# m13temp.net
KiCad netlist of a schematic drawn in Altium Designer
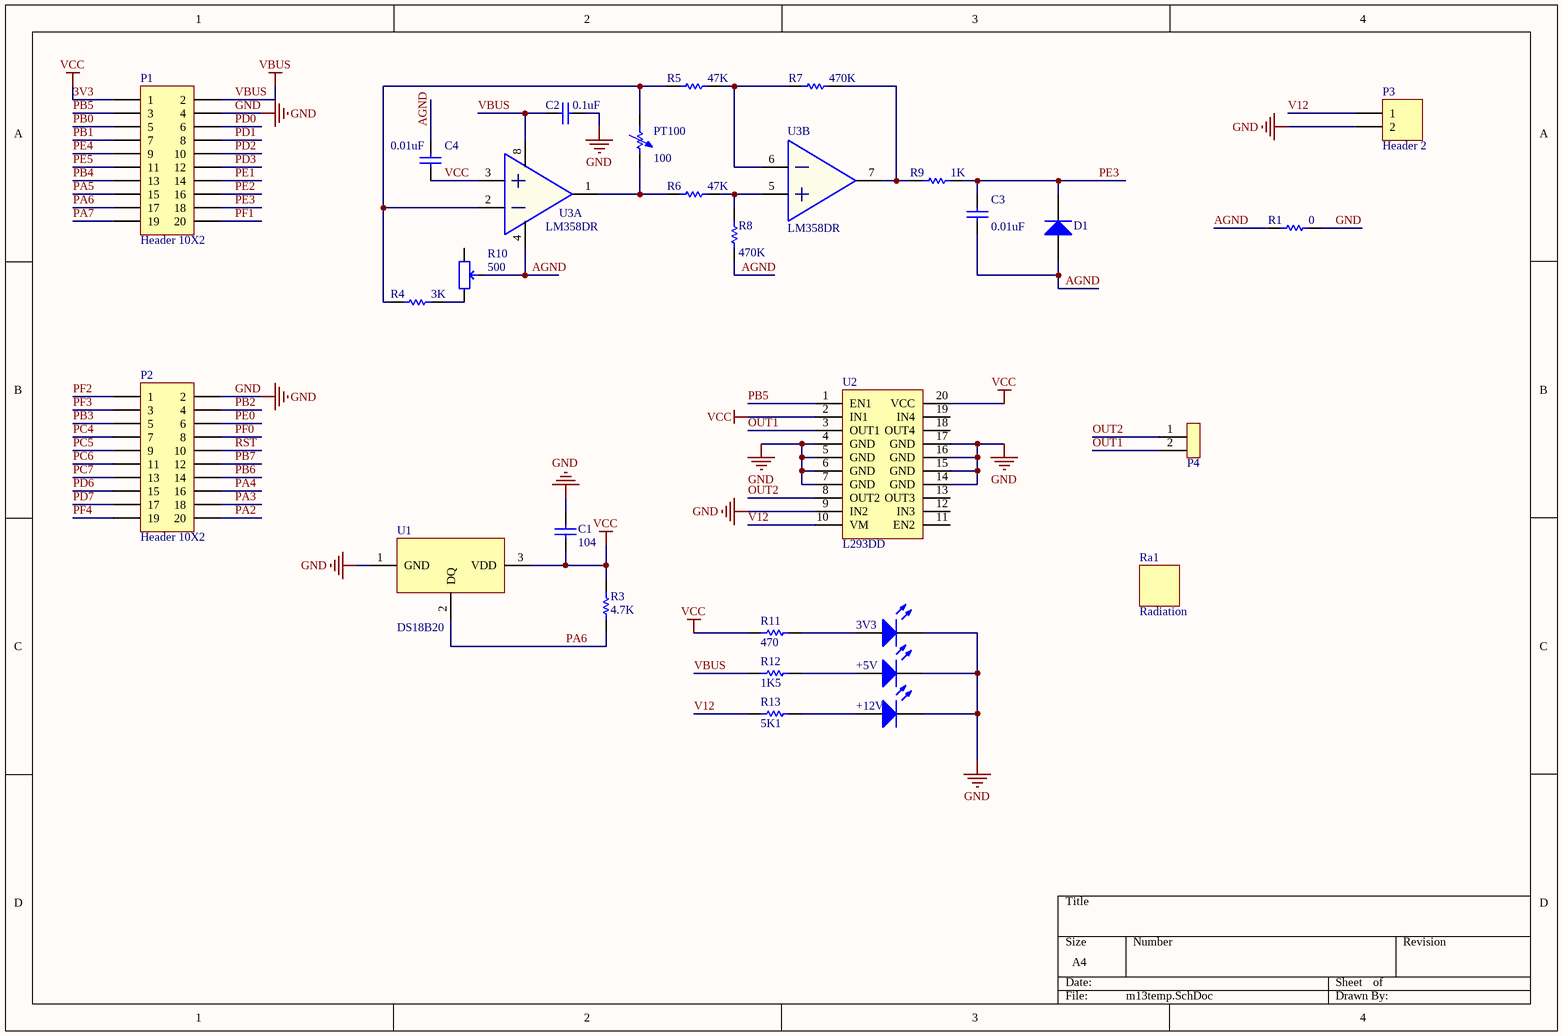
[diagram p0: m13temp.SchDoc]

(export (version "E")
  (design (tool "Eeschema 10.0.6"))
  (components
    (comp (ref "+5V")
      (value "LED2")
      (footprint "LED_0603_RED")
      (description "Typical RED, GREEN, YELLOW, AMBER GaAs LED")
      (fields (field (name "PUBLISHER") "Altium Limited"))
      (libsource (lib "Miscellaneous Devices") (part "LED2"))
    )
    (comp (ref "+12V")
      (value "LED2")
      (footprint "LED_0603_RED")
      (description "Typical RED, GREEN, YELLOW, AMBER GaAs LED")
      (fields (field (name "PUBLISHER") "Altium Limited"))
      (libsource (lib "Miscellaneous Devices") (part "LED2"))
    )
    (comp (ref "3V3")
      (value "LED2")
      (footprint "LED_0603_RED")
      (description "Typical RED, GREEN, YELLOW, AMBER GaAs LED")
      (fields (field (name "PUBLISHER") "Altium Limited"))
      (libsource (lib "Miscellaneous Devices") (part "LED2"))
    )
    (comp (ref "C1")
      (value "104")
      (footprint "CAP_0603")
      (description "Capacitor (Semiconductor SIM Model)")
      (fields (field (name "Comment") "Cap Semi") (field (name "PUBLISHER") "Altium Limited"))
      (libsource (lib "Miscellaneous Devices") (part "Cap Semi"))
    )
    (comp (ref "C2")
      (value "0.1uF")
      (footprint "CAP_0603")
      (description "Capacitor (Semiconductor SIM Model)")
      (fields (field (name "Comment") "Cap Semi") (field (name "PUBLISHER") "Altium Limited"))
      (libsource (lib "Miscellaneous Devices") (part "Cap Semi"))
    )
    (comp (ref "C3")
      (value "0.01uF")
      (footprint "CAP_0603")
      (description "Capacitor (Semiconductor SIM Model)")
      (fields (field (name "Comment") "Cap Semi") (field (name "PUBLISHER") "Altium Limited"))
      (libsource (lib "Miscellaneous Devices") (part "Cap Semi"))
    )
    (comp (ref "C4")
      (value "0.01uF")
      (footprint "CAP_0603")
      (description "Capacitor (Semiconductor SIM Model)")
      (fields (field (name "Comment") "Cap Semi") (field (name "PUBLISHER") "Altium Limited"))
      (libsource (lib "Miscellaneous Devices") (part "Cap Semi"))
    )
    (comp (ref "D1")
      (value "1N4728")
      (footprint "DIAO")
      (description "High Conductance Fast Diode")
      (fields (field (name "PUBLISHER") "Altium Limited"))
      (libsource (lib "Miscellaneous Devices") (part "Diode 1N4148"))
    )
    (comp (ref "P1")
      (value "Header 10X2")
      (footprint "HDR2X10")
      (description "Header, 10-Pin, Dual row")
      (fields (field (name "PUBLISHER") "Altium Limited"))
      (libsource (lib "Miscellaneous Connectors") (part "Header 10X2"))
    )
    (comp (ref "P2")
      (value "Header 10X2")
      (footprint "HDR2X10")
      (description "Header, 10-Pin, Dual row")
      (fields (field (name "PUBLISHER") "Altium Limited"))
      (libsource (lib "Miscellaneous Connectors") (part "Header 10X2"))
    )
    (comp (ref "P3")
      (value "Header 2")
      (footprint "MKDSN_2RMI")
      (description "Header, 2-Pin")
      (fields (field (name "PUBLISHER") "Altium Limited"))
      (libsource (lib "Miscellaneous Connectors") (part "Header 2"))
    )
    (comp (ref "P4") (value "Header2") (footprint "XPH2") (libsource (lib "m13") (part "Header2")))
    (comp (ref "PT100")
      (value "100")
      (footprint "m13:PT100")
      (description "Variable Resistor")
      (fields (field (name "Comment") "PT100") (field (name "PUBLISHER") "Altium Limited"))
      (libsource (lib "Miscellaneous Devices") (part "Res Adj1"))
    )
    (comp (ref "R1")
      (value "0")
      (footprint "RES_0603")
      (description "Semiconductor Resistor")
      (fields (field (name "Comment") "Res Semi") (field (name "PUBLISHER") "Altium Limited"))
      (libsource (lib "Miscellaneous Devices") (part "Res Semi"))
    )
    (comp (ref "R3")
      (value "4.7K")
      (footprint "RES_0603")
      (description "Semiconductor Resistor")
      (fields (field (name "Comment") "Res Semi") (field (name "PUBLISHER") "Altium Limited"))
      (libsource (lib "Miscellaneous Devices") (part "Res Semi"))
    )
    (comp (ref "R4")
      (value "3K")
      (footprint "RES_0603")
      (description "Semiconductor Resistor")
      (fields (field (name "Comment") "Res Semi") (field (name "PUBLISHER") "Altium Limited"))
      (libsource (lib "Miscellaneous Devices") (part "Res Semi"))
    )
    (comp (ref "R5")
      (value "47K")
      (footprint "RES_0603")
      (description "Semiconductor Resistor")
      (fields (field (name "Comment") "Res Semi") (field (name "PUBLISHER") "Altium Limited"))
      (libsource (lib "Miscellaneous Devices") (part "Res Semi"))
    )
    (comp (ref "R6")
      (value "47K")
      (footprint "RES_0603")
      (description "Semiconductor Resistor")
      (fields (field (name "Comment") "Res Semi") (field (name "PUBLISHER") "Altium Limited"))
      (libsource (lib "Miscellaneous Devices") (part "Res Semi"))
    )
    (comp (ref "R7")
      (value "470K")
      (footprint "RES_0603")
      (description "Semiconductor Resistor")
      (fields (field (name "Comment") "Res Semi") (field (name "PUBLISHER") "Altium Limited"))
      (libsource (lib "Miscellaneous Devices") (part "Res Semi"))
    )
    (comp (ref "R8")
      (value "470K")
      (footprint "RES_0603")
      (description "Semiconductor Resistor")
      (fields (field (name "Comment") "Res Semi") (field (name "PUBLISHER") "Altium Limited"))
      (libsource (lib "Miscellaneous Devices") (part "Res Semi"))
    )
    (comp (ref "R9")
      (value "1K")
      (footprint "RES_0603")
      (description "Semiconductor Resistor")
      (fields (field (name "Comment") "Res Semi") (field (name "PUBLISHER") "Altium Limited"))
      (libsource (lib "Miscellaneous Devices") (part "Res Semi"))
    )
    (comp (ref "R10")
      (value "500")
      (footprint "PCB_Passive:RES_TRIMMER")
      (description "Resistor")
      (fields (field (name "Comment") "Res_Trimmer"))
      (libsource (lib "SCH_Passive") (part "Res_Trimmer"))
    )
    (comp (ref "R11")
      (value "470")
      (footprint "RES_0603")
      (description "Semiconductor Resistor")
      (fields (field (name "Comment") "Res Semi") (field (name "PUBLISHER") "Altium Limited"))
      (libsource (lib "Miscellaneous Devices") (part "Res Semi"))
    )
    (comp (ref "R12")
      (value "1K5")
      (footprint "RES_0603")
      (description "Semiconductor Resistor")
      (fields (field (name "Comment") "Res Semi") (field (name "PUBLISHER") "Altium Limited"))
      (libsource (lib "Miscellaneous Devices") (part "Res Semi"))
    )
    (comp (ref "R13")
      (value "5K1")
      (footprint "RES_0603")
      (description "Semiconductor Resistor")
      (fields (field (name "Comment") "Res Semi") (field (name "PUBLISHER") "Altium Limited"))
      (libsource (lib "Miscellaneous Devices") (part "Res Semi"))
    )
    (comp (ref "Ra1") (value "Radiation") (footprint "Radiation") (libsource (lib "m13") (part "Radiation")))
    (comp (ref "U1")
      (value "DS18B20")
      (footprint "TO-92")
      (description "Programmable Resolution  1-Wire Digital Thermometer")
      (libsource (lib "m13") (part "DS18B20"))
    )
    (comp (ref "U2")
      (value "L293DD")
      (footprint "SOP20")
      (description "L293DD MOTOR")
      (libsource (lib "m13") (part "L293DD"))
    )
    (comp (ref "U3")
      (value "LM358DR")
      (footprint "SOIC_8")
      (description "Dual Operational Amplifiers")
      (libsource (lib "m13") (part "LM358DR"))
    )
  )
  (nets
    (net (code "1") (name "/AGND") (class "Default")
      (node (ref "C3") (pin "1") (pinfunction "1_1") (pintype "passive"))
      (node (ref "C4") (pin "2") (pinfunction "2_2") (pintype "passive"))
      (node (ref "D1") (pin "1") (pinfunction "A_1") (pintype "passive"))
      (node (ref "R1") (pin "2") (pinfunction "2_2") (pintype "passive"))
      (node (ref "R10") (pin "2") (pinfunction "W_2") (pintype "passive"))
      (node (ref "R8") (pin "1") (pinfunction "1_1") (pintype "passive"))
      (node (ref "U3") (pin "4") (pinfunction "GND_4") (pintype "passive"))
    )
    (net (code "2") (name "/OUT1") (class "Default")
      (node (ref "P4") (pin "2") (pinfunction "2_2") (pintype "passive"))
      (node (ref "U2") (pin "3") (pinfunction "OUT1_3") (pintype "passive"))
    )
    (net (code "3") (name "/OUT2") (class "Default")
      (node (ref "P4") (pin "1") (pinfunction "1_1") (pintype "passive"))
      (node (ref "U2") (pin "8") (pinfunction "OUT2_8") (pintype "passive"))
    )
    (net (code "4") (name "/PA2") (class "Default")
      (node (ref "P2") (pin "20") (pinfunction "20_20") (pintype "passive"))
    )
    (net (code "5") (name "/PA3") (class "Default")
      (node (ref "P2") (pin "18") (pinfunction "18_18") (pintype "passive"))
    )
    (net (code "6") (name "/PA4") (class "Default")
      (node (ref "P2") (pin "16") (pinfunction "16_16") (pintype "passive"))
    )
    (net (code "7") (name "/PA5") (class "Default")
      (node (ref "P1") (pin "15") (pinfunction "15_15") (pintype "passive"))
    )
    (net (code "8") (name "/PA6") (class "Default")
      (node (ref "P1") (pin "17") (pinfunction "17_17") (pintype "passive"))
      (node (ref "R3") (pin "2") (pinfunction "2_2") (pintype "passive"))
      (node (ref "U1") (pin "2") (pinfunction "DQ_2") (pintype "passive"))
    )
    (net (code "9") (name "/PA7") (class "Default")
      (node (ref "P1") (pin "19") (pinfunction "19_19") (pintype "passive"))
    )
    (net (code "10") (name "/PB0") (class "Default")
      (node (ref "P1") (pin "5") (pinfunction "5_5") (pintype "passive"))
    )
    (net (code "11") (name "/PB1") (class "Default")
      (node (ref "P1") (pin "7") (pinfunction "7_7") (pintype "passive"))
    )
    (net (code "12") (name "/PB2") (class "Default")
      (node (ref "P2") (pin "4") (pinfunction "4_4") (pintype "passive"))
    )
    (net (code "13") (name "/PB3") (class "Default")
      (node (ref "P2") (pin "5") (pinfunction "5_5") (pintype "passive"))
    )
    (net (code "14") (name "/PB4") (class "Default")
      (node (ref "P1") (pin "13") (pinfunction "13_13") (pintype "passive"))
    )
    (net (code "15") (name "/PB5") (class "Default")
      (node (ref "P1") (pin "3") (pinfunction "3_3") (pintype "passive"))
      (node (ref "U2") (pin "1") (pinfunction "EN1_1") (pintype "passive"))
    )
    (net (code "16") (name "/PB6") (class "Default")
      (node (ref "P2") (pin "14") (pinfunction "14_14") (pintype "passive"))
    )
    (net (code "17") (name "/PB7") (class "Default")
      (node (ref "P2") (pin "12") (pinfunction "12_12") (pintype "passive"))
    )
    (net (code "18") (name "/PC4") (class "Default")
      (node (ref "P2") (pin "7") (pinfunction "7_7") (pintype "passive"))
    )
    (net (code "19") (name "/PC5") (class "Default")
      (node (ref "P2") (pin "9") (pinfunction "9_9") (pintype "passive"))
    )
    (net (code "20") (name "/PC6") (class "Default")
      (node (ref "P2") (pin "11") (pinfunction "11_11") (pintype "passive"))
    )
    (net (code "21") (name "/PC7") (class "Default")
      (node (ref "P2") (pin "13") (pinfunction "13_13") (pintype "passive"))
    )
    (net (code "22") (name "/PD0") (class "Default")
      (node (ref "P1") (pin "6") (pinfunction "6_6") (pintype "passive"))
    )
    (net (code "23") (name "/PD1") (class "Default")
      (node (ref "P1") (pin "8") (pinfunction "8_8") (pintype "passive"))
    )
    (net (code "24") (name "/PD2") (class "Default")
      (node (ref "P1") (pin "10") (pinfunction "10_10") (pintype "passive"))
    )
    (net (code "25") (name "/PD3") (class "Default")
      (node (ref "P1") (pin "12") (pinfunction "12_12") (pintype "passive"))
    )
    (net (code "26") (name "/PD6") (class "Default")
      (node (ref "P2") (pin "15") (pinfunction "15_15") (pintype "passive"))
    )
    (net (code "27") (name "/PD7") (class "Default")
      (node (ref "P2") (pin "17") (pinfunction "17_17") (pintype "passive"))
    )
    (net (code "28") (name "/PE0") (class "Default")
      (node (ref "P2") (pin "6") (pinfunction "6_6") (pintype "passive"))
    )
    (net (code "29") (name "/PE1") (class "Default")
      (node (ref "P1") (pin "14") (pinfunction "14_14") (pintype "passive"))
    )
    (net (code "30") (name "/PE2") (class "Default")
      (node (ref "P1") (pin "16") (pinfunction "16_16") (pintype "passive"))
    )
    (net (code "31") (name "/PE3") (class "Default")
      (node (ref "C3") (pin "2") (pinfunction "2_2") (pintype "passive"))
      (node (ref "D1") (pin "2") (pinfunction "K_2") (pintype "passive"))
      (node (ref "P1") (pin "18") (pinfunction "18_18") (pintype "passive"))
      (node (ref "R9") (pin "1") (pinfunction "1_1") (pintype "passive"))
    )
    (net (code "32") (name "/PE4") (class "Default")
      (node (ref "P1") (pin "9") (pinfunction "9_9") (pintype "passive"))
    )
    (net (code "33") (name "/PE5") (class "Default")
      (node (ref "P1") (pin "11") (pinfunction "11_11") (pintype "passive"))
    )
    (net (code "34") (name "/PF0") (class "Default")
      (node (ref "P2") (pin "8") (pinfunction "8_8") (pintype "passive"))
    )
    (net (code "35") (name "/PF1") (class "Default")
      (node (ref "P1") (pin "20") (pinfunction "20_20") (pintype "passive"))
    )
    (net (code "36") (name "/PF2") (class "Default")
      (node (ref "P2") (pin "1") (pinfunction "1_1") (pintype "passive"))
    )
    (net (code "37") (name "/PF3") (class "Default")
      (node (ref "P2") (pin "3") (pinfunction "3_3") (pintype "passive"))
    )
    (net (code "38") (name "/PF4") (class "Default")
      (node (ref "P2") (pin "19") (pinfunction "19_19") (pintype "passive"))
    )
    (net (code "39") (name "/RST") (class "Default")
      (node (ref "P2") (pin "10") (pinfunction "10_10") (pintype "passive"))
    )
    (net (code "40") (name "/V12") (class "Default")
      (node (ref "P3") (pin "1") (pinfunction "1_1") (pintype "passive"))
      (node (ref "R13") (pin "1") (pinfunction "1_1") (pintype "passive"))
      (node (ref "U2") (pin "10") (pinfunction "VM_10") (pintype "passive"))
    )
    (net (code "41") (name "GND") (class "Default")
      (node (ref "+12V") (pin "2") (pinfunction "K_2") (pintype "passive"))
      (node (ref "+5V") (pin "2") (pinfunction "K_2") (pintype "passive"))
      (node (ref "3V3") (pin "2") (pinfunction "K_2") (pintype "passive"))
      (node (ref "C1") (pin "1") (pinfunction "1_1") (pintype "passive"))
      (node (ref "C2") (pin "2") (pinfunction "2_2") (pintype "passive"))
      (node (ref "P1") (pin "4") (pinfunction "4_4") (pintype "passive"))
      (node (ref "P2") (pin "2") (pinfunction "2_2") (pintype "passive"))
      (node (ref "P3") (pin "2") (pinfunction "2_2") (pintype "passive"))
      (node (ref "R1") (pin "1") (pinfunction "1_1") (pintype "passive"))
      (node (ref "U1") (pin "1") (pinfunction "GND_1") (pintype "passive"))
      (node (ref "U2") (pin "14") (pinfunction "GND_14") (pintype "passive"))
      (node (ref "U2") (pin "15") (pinfunction "GND_15") (pintype "passive"))
      (node (ref "U2") (pin "16") (pinfunction "GND_16") (pintype "passive"))
      (node (ref "U2") (pin "17") (pinfunction "GND_17") (pintype "passive"))
      (node (ref "U2") (pin "4") (pinfunction "GND_4") (pintype "passive"))
      (node (ref "U2") (pin "5") (pinfunction "GND_5") (pintype "passive"))
      (node (ref "U2") (pin "6") (pinfunction "GND_6") (pintype "passive"))
      (node (ref "U2") (pin "7") (pinfunction "GND_7") (pintype "passive"))
      (node (ref "U2") (pin "9") (pinfunction "IN2_9") (pintype "passive"))
    )
    (net (code "42") (name "Net-(+5V-A)") (class "Default")
      (node (ref "+5V") (pin "1") (pinfunction "A_1") (pintype "passive"))
      (node (ref "R12") (pin "2") (pinfunction "2_2") (pintype "passive"))
    )
    (net (code "43") (name "Net-(+12V-A)") (class "Default")
      (node (ref "+12V") (pin "1") (pinfunction "A_1") (pintype "passive"))
      (node (ref "R13") (pin "2") (pinfunction "2_2") (pintype "passive"))
    )
    (net (code "44") (name "Net-(3V3-A)") (class "Default")
      (node (ref "3V3") (pin "1") (pinfunction "A_1") (pintype "passive"))
      (node (ref "R11") (pin "2") (pinfunction "2_2") (pintype "passive"))
    )
    (net (code "45") (name "Net-(R10-CCW)") (class "Default")
      (node (ref "R10") (pin "1") (pinfunction "CCW_1") (pintype "passive"))
      (node (ref "R4") (pin "2") (pinfunction "2_2") (pintype "passive"))
    )
    (net (code "46") (name "Net-(U3A-1IN-)") (class "Default")
      (node (ref "PT100") (pin "1") (pinfunction "1_1") (pintype "passive"))
      (node (ref "R4") (pin "1") (pinfunction "1_1") (pintype "passive"))
      (node (ref "R5") (pin "1") (pinfunction "1_1") (pintype "passive"))
      (node (ref "U3") (pin "2") (pinfunction "1IN-_2") (pintype "passive"))
    )
    (net (code "47") (name "Net-(U3A-1OUT)") (class "Default")
      (node (ref "PT100") (pin "2") (pinfunction "2_2") (pintype "passive"))
      (node (ref "R6") (pin "1") (pinfunction "1_1") (pintype "passive"))
      (node (ref "U3") (pin "1") (pinfunction "1OUT_1") (pintype "passive"))
    )
    (net (code "48") (name "Net-(U3B-2IN+)") (class "Default")
      (node (ref "R6") (pin "2") (pinfunction "2_2") (pintype "passive"))
      (node (ref "R8") (pin "2") (pinfunction "2_2") (pintype "passive"))
      (node (ref "U3") (pin "5") (pinfunction "2IN+_5") (pintype "passive"))
    )
    (net (code "49") (name "Net-(U3B-2IN-)") (class "Default")
      (node (ref "R5") (pin "2") (pinfunction "2_2") (pintype "passive"))
      (node (ref "R7") (pin "1") (pinfunction "1_1") (pintype "passive"))
      (node (ref "U3") (pin "6") (pinfunction "2IN-_6") (pintype "passive"))
    )
    (net (code "50") (name "Net-(U3B-2OUT)") (class "Default")
      (node (ref "R7") (pin "2") (pinfunction "2_2") (pintype "passive"))
      (node (ref "R9") (pin "2") (pinfunction "2_2") (pintype "passive"))
      (node (ref "U3") (pin "7") (pinfunction "2OUT_7") (pintype "passive"))
    )
    (net (code "51") (name "VBUS") (class "Default")
      (node (ref "C2") (pin "1") (pinfunction "1_1") (pintype "passive"))
      (node (ref "P1") (pin "2") (pinfunction "2_2") (pintype "passive"))
      (node (ref "R12") (pin "1") (pinfunction "1_1") (pintype "passive"))
      (node (ref "U3") (pin "8") (pinfunction "VCC_8") (pintype "passive"))
    )
    (net (code "52") (name "VCC") (class "Default")
      (node (ref "C1") (pin "2") (pinfunction "2_2") (pintype "passive"))
      (node (ref "C4") (pin "1") (pinfunction "1_1") (pintype "passive"))
      (node (ref "P1") (pin "1") (pinfunction "1_1") (pintype "passive"))
      (node (ref "R11") (pin "1") (pinfunction "1_1") (pintype "passive"))
      (node (ref "R3") (pin "1") (pinfunction "1_1") (pintype "passive"))
      (node (ref "U1") (pin "3") (pinfunction "VDD_3") (pintype "passive"))
      (node (ref "U2") (pin "2") (pinfunction "IN1_2") (pintype "passive"))
      (node (ref "U2") (pin "20") (pinfunction "VCC_20") (pintype "passive"))
      (node (ref "U3") (pin "3") (pinfunction "1IN+_3") (pintype "passive"))
    )
    (net (code "53") (name "unconnected-(R10-CW-Pad3)") (class "Default")
      (node (ref "R10") (pin "3") (pinfunction "CW_3") (pintype "passive"))
    )
    (net (code "54") (name "unconnected-(U2-EN2-Pad11)") (class "Default")
      (node (ref "U2") (pin "11") (pinfunction "EN2_11") (pintype "passive"))
    )
    (net (code "55") (name "unconnected-(U2-IN3-Pad12)") (class "Default")
      (node (ref "U2") (pin "12") (pinfunction "IN3_12") (pintype "passive"))
    )
    (net (code "56") (name "unconnected-(U2-IN4-Pad19)") (class "Default")
      (node (ref "U2") (pin "19") (pinfunction "IN4_19") (pintype "passive"))
    )
    (net (code "57") (name "unconnected-(U2-OUT3-Pad13)") (class "Default")
      (node (ref "U2") (pin "13") (pinfunction "OUT3_13") (pintype "passive"))
    )
    (net (code "58") (name "unconnected-(U2-OUT4-Pad18)") (class "Default")
      (node (ref "U2") (pin "18") (pinfunction "OUT4_18") (pintype "passive"))
    )
  )
)
